# IV_sensing.net
KiCad netlist of a schematic drawn in Altium Designer
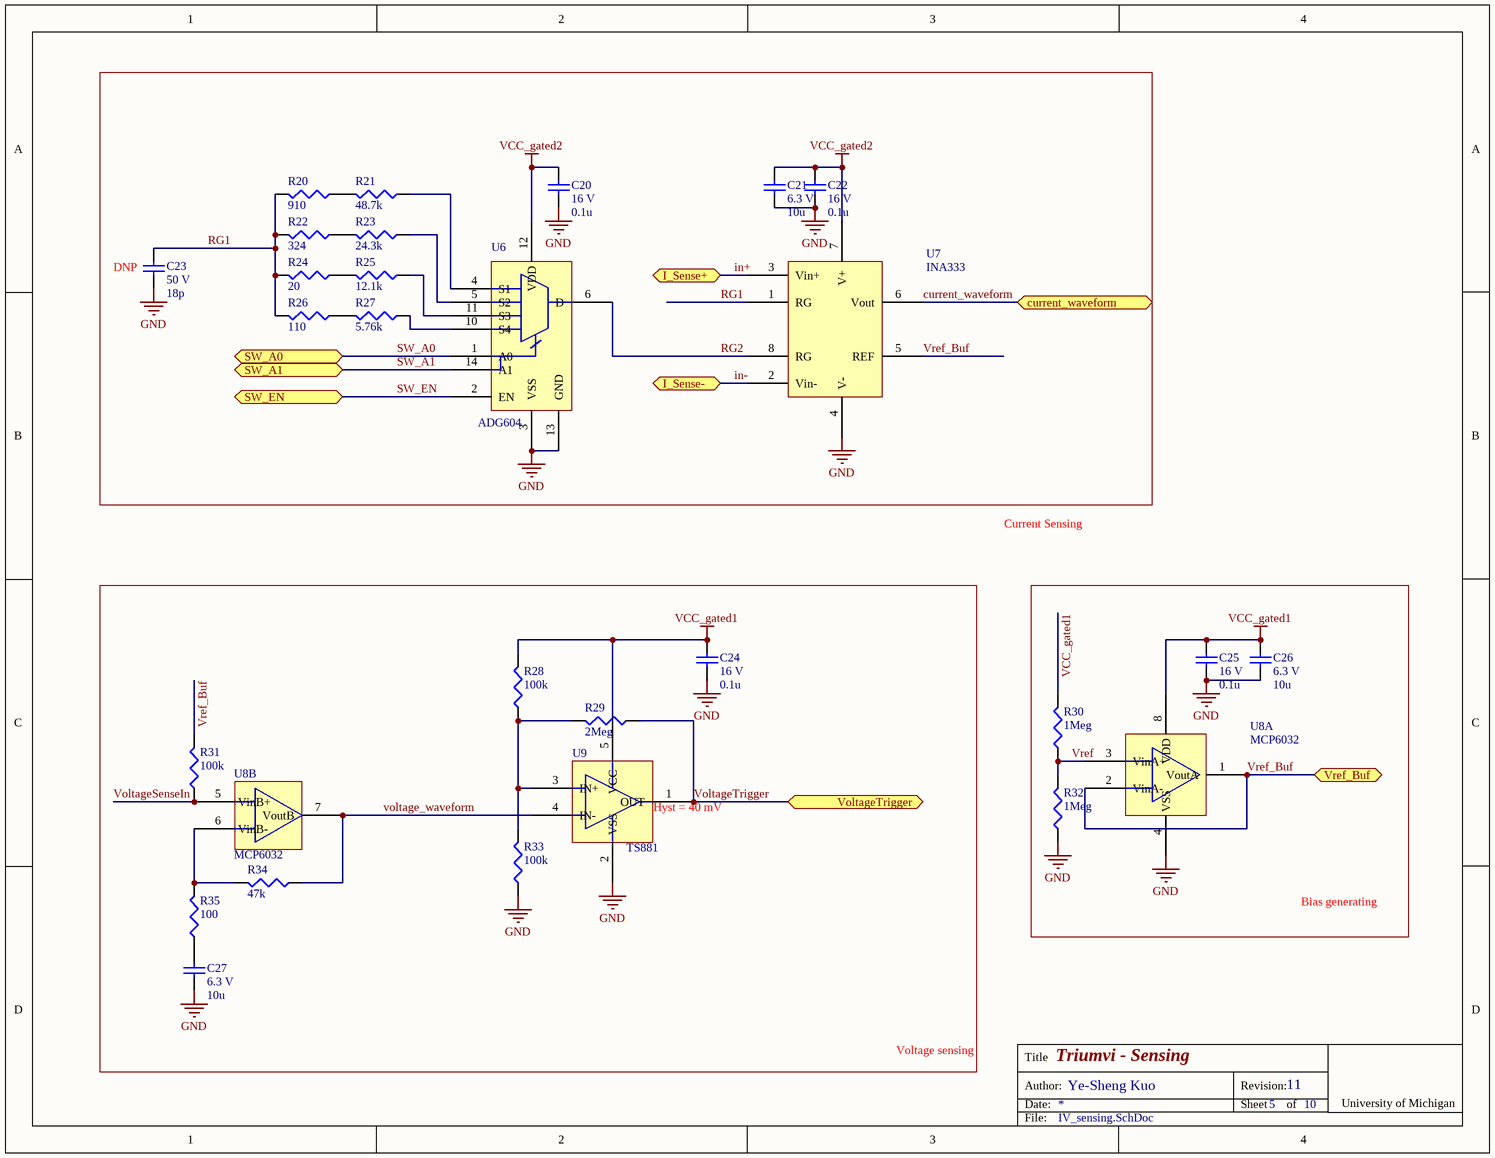
[diagram p0: IV_sensing.SchDoc]

(export (version "E")
  (design (tool "Eeschema 10.0.6"))
  (components
    (comp (ref "C20")
      (value "0.1u")
      (footprint "0402")
      (description "0.10µF ±10% 16V Ceramic Capacitor X7R 0402")
      (fields
        (field (name "VOLTAGE RATED") "16 V")
        (field (name "TOLERANCE") "10%")
        (field (name "MANUFACTURER PART NUMBER") "GRM155R71C104KA88D")
      )
      (libsource (lib "capacitors") (part "GRM155R71C104KA88D"))
    )
    (comp (ref "C21")
      (value "10u")
      (footprint "0603")
      (description "10µF ±20% 6.3V Ceramic Capacitor X5R 0603")
      (fields
        (field (name "VOLTAGE RATED") "6.3 V")
        (field (name "TOLERANCE") "20%")
        (field (name "MANUFACTURER PART NUMBER") "C1608X5R0J106M080AB")
      )
      (libsource (lib "capacitors") (part "C1608X5R0J106M080AB"))
    )
    (comp (ref "C22")
      (value "0.1u")
      (footprint "0402")
      (description "0.10µF ±10% 16V Ceramic Capacitor X7R 0402")
      (fields
        (field (name "VOLTAGE RATED") "16 V")
        (field (name "TOLERANCE") "10%")
        (field (name "MANUFACTURER PART NUMBER") "GRM155R71C104KA88D")
      )
      (libsource (lib "capacitors") (part "GRM155R71C104KA88D"))
    )
    (comp (ref "C23")
      (value "18p")
      (footprint "0402")
      (description "18pF ±2% 50V Ceramic Capacitor C0G, NP0 0402")
      (fields
        (field (name "TOLERANCE") "2%")
        (field (name "MANUFACTURER PART NUMBER") "500R07S180GV4T")
        (field (name "VOLTAGE RATED") "50 V")
      )
      (libsource (lib "capacitors") (part "500R07S180GV4T"))
    )
    (comp (ref "C24")
      (value "0.1u")
      (footprint "0402")
      (description "0.10µF ±10% 16V Ceramic Capacitor X7R 0402")
      (fields
        (field (name "VOLTAGE RATED") "16 V")
        (field (name "TOLERANCE") "10%")
        (field (name "MANUFACTURER PART NUMBER") "GRM155R71C104KA88D")
      )
      (libsource (lib "capacitors") (part "GRM155R71C104KA88D"))
    )
    (comp (ref "C25")
      (value "0.1u")
      (footprint "0402")
      (description "0.10µF ±10% 16V Ceramic Capacitor X7R 0402")
      (fields
        (field (name "VOLTAGE RATED") "16 V")
        (field (name "TOLERANCE") "10%")
        (field (name "MANUFACTURER PART NUMBER") "GRM155R71C104KA88D")
      )
      (libsource (lib "capacitors") (part "GRM155R71C104KA88D"))
    )
    (comp (ref "C26")
      (value "10u")
      (footprint "0603")
      (description "10µF ±20% 6.3V Ceramic Capacitor X5R 0603")
      (fields
        (field (name "VOLTAGE RATED") "6.3 V")
        (field (name "TOLERANCE") "20%")
        (field (name "MANUFACTURER PART NUMBER") "C1608X5R0J106M080AB")
      )
      (libsource (lib "capacitors") (part "C1608X5R0J106M080AB"))
    )
    (comp (ref "C27")
      (value "10u")
      (footprint "0603")
      (description "10µF ±20% 6.3V Ceramic Capacitor X5R 0603")
      (fields
        (field (name "VOLTAGE RATED") "6.3 V")
        (field (name "TOLERANCE") "20%")
        (field (name "MANUFACTURER PART NUMBER") "C1608X5R0J106M080AB")
      )
      (libsource (lib "capacitors") (part "C1608X5R0J106M080AB"))
    )
    (comp (ref "R20")
      (value "910")
      (footprint "0402")
      (description "RES SMD 910 OHM 1% 1/16W 0402")
      (fields
        (field (name "MANUFACTURER PART NUMBER") "CRCW0402910RFKED")
        (field (name "MANUFACTURER") "Vishay Dale")
      )
      (libsource (lib "resistors") (part "CRCW0402910RFKED"))
    )
    (comp (ref "R21")
      (value "48.7k")
      (footprint "0402")
      (description "RES SMD 48.7K OHM 0.5% 1/16W 0402")
      (fields
        (field (name "MANUFACTURER PART NUMBER") "RT0402DRD0748K7L")
        (field (name "MANUFACTURER") "Yageo")
      )
      (libsource (lib "resistors") (part "RT0402DRD0748K7L"))
    )
    (comp (ref "R22")
      (value "324")
      (footprint "0402")
      (description "RES SMD 324 OHM 1% 1/16W 0402")
      (fields
        (field (name "MANUFACTURER PART NUMBER") "CRCW0402324RFKED")
        (field (name "MANUFACTURER") "Vishay Dale")
      )
      (libsource (lib "resistors") (part "CRCW0402324RFKED"))
    )
    (comp (ref "R23")
      (value "24.3k")
      (footprint "0402")
      (description "RES SMD 24.3K OHM 0.5% 1/16W 0402")
      (fields
        (field (name "MANUFACTURER PART NUMBER") "RC0402FR-0724K3L")
        (field (name "MANUFACTURER") "Yageo")
      )
      (libsource (lib "resistors") (part "RC0402FR-0724K3L"))
    )
    (comp (ref "R24")
      (value "20")
      (footprint "0402")
      (description "RES SMD 20 OHM 1% 1/16W 0402")
      (fields
        (field (name "MANUFACTURER PART NUMBER") "CRCW040220R0FKED")
        (field (name "MANUFACTURER") "Vishay Dale")
      )
      (libsource (lib "resistors") (part "CRCW040220R0FKED"))
    )
    (comp (ref "R25")
      (value "12.1k")
      (footprint "0402")
      (description "RES SMD 12.1K OHM 1% 1/16W 0402")
      (fields
        (field (name "MANUFACTURER PART NUMBER") "CRCW040212K1FKED")
        (field (name "MANUFACTURER") "Vishay Dale")
      )
      (libsource (lib "resistors") (part "CRCW040212K1FKED"))
    )
    (comp (ref "R26")
      (value "110")
      (footprint "0402")
      (description "RES SMD 110 OHM 1% 1/16W 0402")
      (fields
        (field (name "MANUFACTURER PART NUMBER") "CRCW0402110RFKED")
        (field (name "MANUFACTURER") "Vishay Dale")
      )
      (libsource (lib "resistors") (part "CRCW0402110RFKED"))
    )
    (comp (ref "R27")
      (value "5.76k")
      (footprint "0402")
      (description "RES SMD 5.76K OHM 0.5% 1/16W 0402")
      (fields
        (field (name "MANUFACTURER PART NUMBER") "RC0402FR-075K76L")
        (field (name "MANUFACTURER") "Yageo")
      )
      (libsource (lib "resistors") (part "RC0402FR-075K76L"))
    )
    (comp (ref "R28")
      (value "100k")
      (footprint "0402")
      (description "RES SMD 100K OHM 1% 1/16W 0402")
      (fields (field (name "TOLERANCE") "1%") (field (name "POWER") "1/16 W"))
      (libsource (lib "resistors") (part "CRCW0402100KFKED"))
    )
    (comp (ref "R29")
      (value "2Meg")
      (footprint "0402")
      (description "RES SMD 2M OHM 1% 1/16W 0402")
      (fields (field (name "TOLERANCE") "1%") (field (name "POWER") "1/16 W"))
      (libsource (lib "resistors") (part "CRCW04022M00FKED"))
    )
    (comp (ref "R30")
      (value "1Meg")
      (footprint "0402")
      (description "RES SMD 1M OHM 1% 1/16W 0402")
      (fields (field (name "TOLERANCE") "1%") (field (name "POWER") "1/16 W"))
      (libsource (lib "resistors") (part "CRCW04021M00FKED"))
    )
    (comp (ref "R31")
      (value "100k")
      (footprint "0402")
      (description "RES SMD 100K OHM 1% 1/16W 0402")
      (fields (field (name "TOLERANCE") "1%") (field (name "POWER") "1/16 W"))
      (libsource (lib "resistors") (part "CRCW0402100KFKED"))
    )
    (comp (ref "R32")
      (value "1Meg")
      (footprint "0402")
      (description "RES SMD 1M OHM 1% 1/16W 0402")
      (fields (field (name "TOLERANCE") "1%") (field (name "POWER") "1/16 W"))
      (libsource (lib "resistors") (part "CRCW04021M00FKED"))
    )
    (comp (ref "R33")
      (value "100k")
      (footprint "0402")
      (description "RES SMD 100K OHM 1% 1/16W 0402")
      (fields (field (name "TOLERANCE") "1%") (field (name "POWER") "1/16 W"))
      (libsource (lib "resistors") (part "CRCW0402100KFKED"))
    )
    (comp (ref "R34")
      (value "47k")
      (footprint "0402")
      (description "RES SMD 47K OHM 1% 1/16W 0402")
      (fields (field (name "TOLERANCE") "1%") (field (name "POWER") "1/16 W"))
      (libsource (lib "resistors") (part "CRCW040247K0FKED"))
    )
    (comp (ref "R35")
      (value "100")
      (footprint "0402")
      (description "RES SMD 100 OHM 1% 1/16W 0402")
      (fields (field (name "TOLERANCE") "1%") (field (name "POWER") "1/16 W"))
      (libsource (lib "resistors") (part "CRCW0402100RFKED"))
    )
    (comp (ref "U6")
      (value "ADG604")
      (footprint "TSSOP-14")
      (description "1 pC Charge Injection, 100 pA Leakage  CMOS  5 V/5 V/3 V 4-Channel Multiplexer")
      (libsource (lib "multiplexer") (part "ADG604"))
    )
    (comp (ref "U7")
      (value "INA333")
      (footprint "MSOP-8")
      (description "Micro-Power (50uA), Zero-Drift, Rail-to-Rail Out  Instrumentation Amplifier")
      (libsource (lib "amplifier") (part "INA333"))
    )
    (comp (ref "U8")
      (value "MCP6032")
      (footprint "MSOP-8")
      (description "0.9 µA, High Precision Op Amps")
      (libsource (lib "amplifier") (part "MCP6032"))
    )
    (comp (ref "U9")
      (value "TS881")
      (footprint "SC70-5")
      (description "Rail-to-rail 0.9 V nanopower comparator")
      (libsource (lib "comparators") (part "TS881"))
    )
  )
  (nets
    (net (code "1") (name "/RG1") (class "Default")
      (node (ref "C23") (pin "1") (pintype "passive"))
      (node (ref "R20") (pin "1") (pintype "passive"))
      (node (ref "R22") (pin "1") (pintype "passive"))
      (node (ref "R24") (pin "1") (pintype "passive"))
      (node (ref "R26") (pin "1") (pintype "passive"))
      (node (ref "U7") (pin "1") (pinfunction "RG_1") (pintype "passive"))
    )
    (net (code "2") (name "/RG2") (class "Default")
      (node (ref "U6") (pin "6") (pinfunction "D_6") (pintype "passive"))
      (node (ref "U7") (pin "8") (pinfunction "RG_8") (pintype "passive"))
    )
    (net (code "3") (name "/SW_A0") (class "Default")
      (node (ref "U6") (pin "1") (pinfunction "A0_1") (pintype "passive"))
    )
    (net (code "4") (name "/SW_A1") (class "Default")
      (node (ref "U6") (pin "14") (pinfunction "A1_14") (pintype "passive"))
    )
    (net (code "5") (name "/SW_EN") (class "Default")
      (node (ref "U6") (pin "2") (pinfunction "EN_2") (pintype "passive"))
    )
    (net (code "6") (name "/VoltageSenseIn") (class "Default")
      (node (ref "R31") (pin "2") (pintype "passive"))
      (node (ref "U8") (pin "5") (pinfunction "VinB+_5") (pintype "passive"))
    )
    (net (code "7") (name "/VoltageTrigger") (class "Default")
      (node (ref "R29") (pin "2") (pintype "passive"))
      (node (ref "U9") (pin "1") (pinfunction "OUT_1") (pintype "passive"))
    )
    (net (code "8") (name "/Vref") (class "Default")
      (node (ref "R30") (pin "2") (pintype "passive"))
      (node (ref "R32") (pin "1") (pintype "passive"))
      (node (ref "U8") (pin "3") (pinfunction "VinA+_3") (pintype "passive"))
    )
    (net (code "9") (name "/Vref_Buf") (class "Default")
      (node (ref "R31") (pin "1") (pintype "passive"))
      (node (ref "U7") (pin "5") (pinfunction "REF_5") (pintype "passive"))
      (node (ref "U8") (pin "1") (pinfunction "VoutA_1") (pintype "passive"))
      (node (ref "U8") (pin "2") (pinfunction "VinA-_2") (pintype "passive"))
    )
    (net (code "10") (name "/current_waveform") (class "Default")
      (node (ref "U7") (pin "6") (pinfunction "Vout_6") (pintype "passive"))
    )
    (net (code "11") (name "/in+") (class "Default")
      (node (ref "U7") (pin "3") (pinfunction "Vin+_3") (pintype "passive"))
    )
    (net (code "12") (name "/in-") (class "Default")
      (node (ref "U7") (pin "2") (pinfunction "Vin-_2") (pintype "passive"))
    )
    (net (code "13") (name "/voltage_waveform") (class "Default")
      (node (ref "R34") (pin "2") (pintype "passive"))
      (node (ref "U8") (pin "7") (pinfunction "VoutB_7") (pintype "passive"))
      (node (ref "U9") (pin "4") (pinfunction "IN-_4") (pintype "passive"))
    )
    (net (code "14") (name "GND") (class "Default")
      (node (ref "C20") (pin "2") (pintype "passive"))
      (node (ref "C21") (pin "2") (pintype "passive"))
      (node (ref "C22") (pin "2") (pintype "passive"))
      (node (ref "C23") (pin "2") (pintype "passive"))
      (node (ref "C24") (pin "2") (pintype "passive"))
      (node (ref "C25") (pin "2") (pintype "passive"))
      (node (ref "C26") (pin "2") (pintype "passive"))
      (node (ref "C27") (pin "2") (pintype "passive"))
      (node (ref "R32") (pin "2") (pintype "passive"))
      (node (ref "R33") (pin "2") (pintype "passive"))
      (node (ref "U6") (pin "13") (pinfunction "GND_13") (pintype "passive"))
      (node (ref "U6") (pin "3") (pinfunction "VSS_3") (pintype "passive"))
      (node (ref "U7") (pin "4") (pinfunction "V-_4") (pintype "passive"))
      (node (ref "U8") (pin "4") (pinfunction "VSS_4") (pintype "passive"))
      (node (ref "U9") (pin "2") (pinfunction "VSS_2") (pintype "passive"))
    )
    (net (code "15") (name "Net-(C27-Pad1)") (class "Default")
      (node (ref "C27") (pin "1") (pintype "passive"))
      (node (ref "R35") (pin "2") (pintype "passive"))
    )
    (net (code "16") (name "Net-(R20-Pad2)") (class "Default")
      (node (ref "R20") (pin "2") (pintype "passive"))
      (node (ref "R21") (pin "1") (pintype "passive"))
    )
    (net (code "17") (name "Net-(R22-Pad2)") (class "Default")
      (node (ref "R22") (pin "2") (pintype "passive"))
      (node (ref "R23") (pin "1") (pintype "passive"))
    )
    (net (code "18") (name "Net-(R24-Pad2)") (class "Default")
      (node (ref "R24") (pin "2") (pintype "passive"))
      (node (ref "R25") (pin "1") (pintype "passive"))
    )
    (net (code "19") (name "Net-(R26-Pad2)") (class "Default")
      (node (ref "R26") (pin "2") (pintype "passive"))
      (node (ref "R27") (pin "1") (pintype "passive"))
    )
    (net (code "20") (name "Net-(U6-S1)") (class "Default")
      (node (ref "R21") (pin "2") (pintype "passive"))
      (node (ref "U6") (pin "4") (pinfunction "S1_4") (pintype "passive"))
    )
    (net (code "21") (name "Net-(U6-S2)") (class "Default")
      (node (ref "R23") (pin "2") (pintype "passive"))
      (node (ref "U6") (pin "5") (pinfunction "S2_5") (pintype "passive"))
    )
    (net (code "22") (name "Net-(U6-S3)") (class "Default")
      (node (ref "R25") (pin "2") (pintype "passive"))
      (node (ref "U6") (pin "11") (pinfunction "S3_11") (pintype "passive"))
    )
    (net (code "23") (name "Net-(U6-S4)") (class "Default")
      (node (ref "R27") (pin "2") (pintype "passive"))
      (node (ref "U6") (pin "10") (pinfunction "S4_10") (pintype "passive"))
    )
    (net (code "24") (name "Net-(U8B-VinB-)") (class "Default")
      (node (ref "R34") (pin "1") (pintype "passive"))
      (node (ref "R35") (pin "1") (pintype "passive"))
      (node (ref "U8") (pin "6") (pinfunction "VinB-_6") (pintype "passive"))
    )
    (net (code "25") (name "Net-(U9-IN+)") (class "Default")
      (node (ref "R28") (pin "2") (pintype "passive"))
      (node (ref "R29") (pin "1") (pintype "passive"))
      (node (ref "R33") (pin "1") (pintype "passive"))
      (node (ref "U9") (pin "3") (pinfunction "IN+_3") (pintype "passive"))
    )
    (net (code "26") (name "VCC_gated1") (class "Default")
      (node (ref "C24") (pin "1") (pintype "passive"))
      (node (ref "C25") (pin "1") (pintype "passive"))
      (node (ref "C26") (pin "1") (pintype "passive"))
      (node (ref "R28") (pin "1") (pintype "passive"))
      (node (ref "R30") (pin "1") (pintype "passive"))
      (node (ref "U8") (pin "8") (pinfunction "VDD_8") (pintype "passive"))
      (node (ref "U9") (pin "5") (pinfunction "VCC_5") (pintype "passive"))
    )
    (net (code "27") (name "VCC_gated2") (class "Default")
      (node (ref "C20") (pin "1") (pintype "passive"))
      (node (ref "C21") (pin "1") (pintype "passive"))
      (node (ref "C22") (pin "1") (pintype "passive"))
      (node (ref "U6") (pin "12") (pinfunction "VDD_12") (pintype "passive"))
      (node (ref "U7") (pin "7") (pinfunction "V+_7") (pintype "passive"))
    )
  )
)
